# 1WireStamp-V01-006.net
KiCad netlist of a schematic drawn in EAGLE
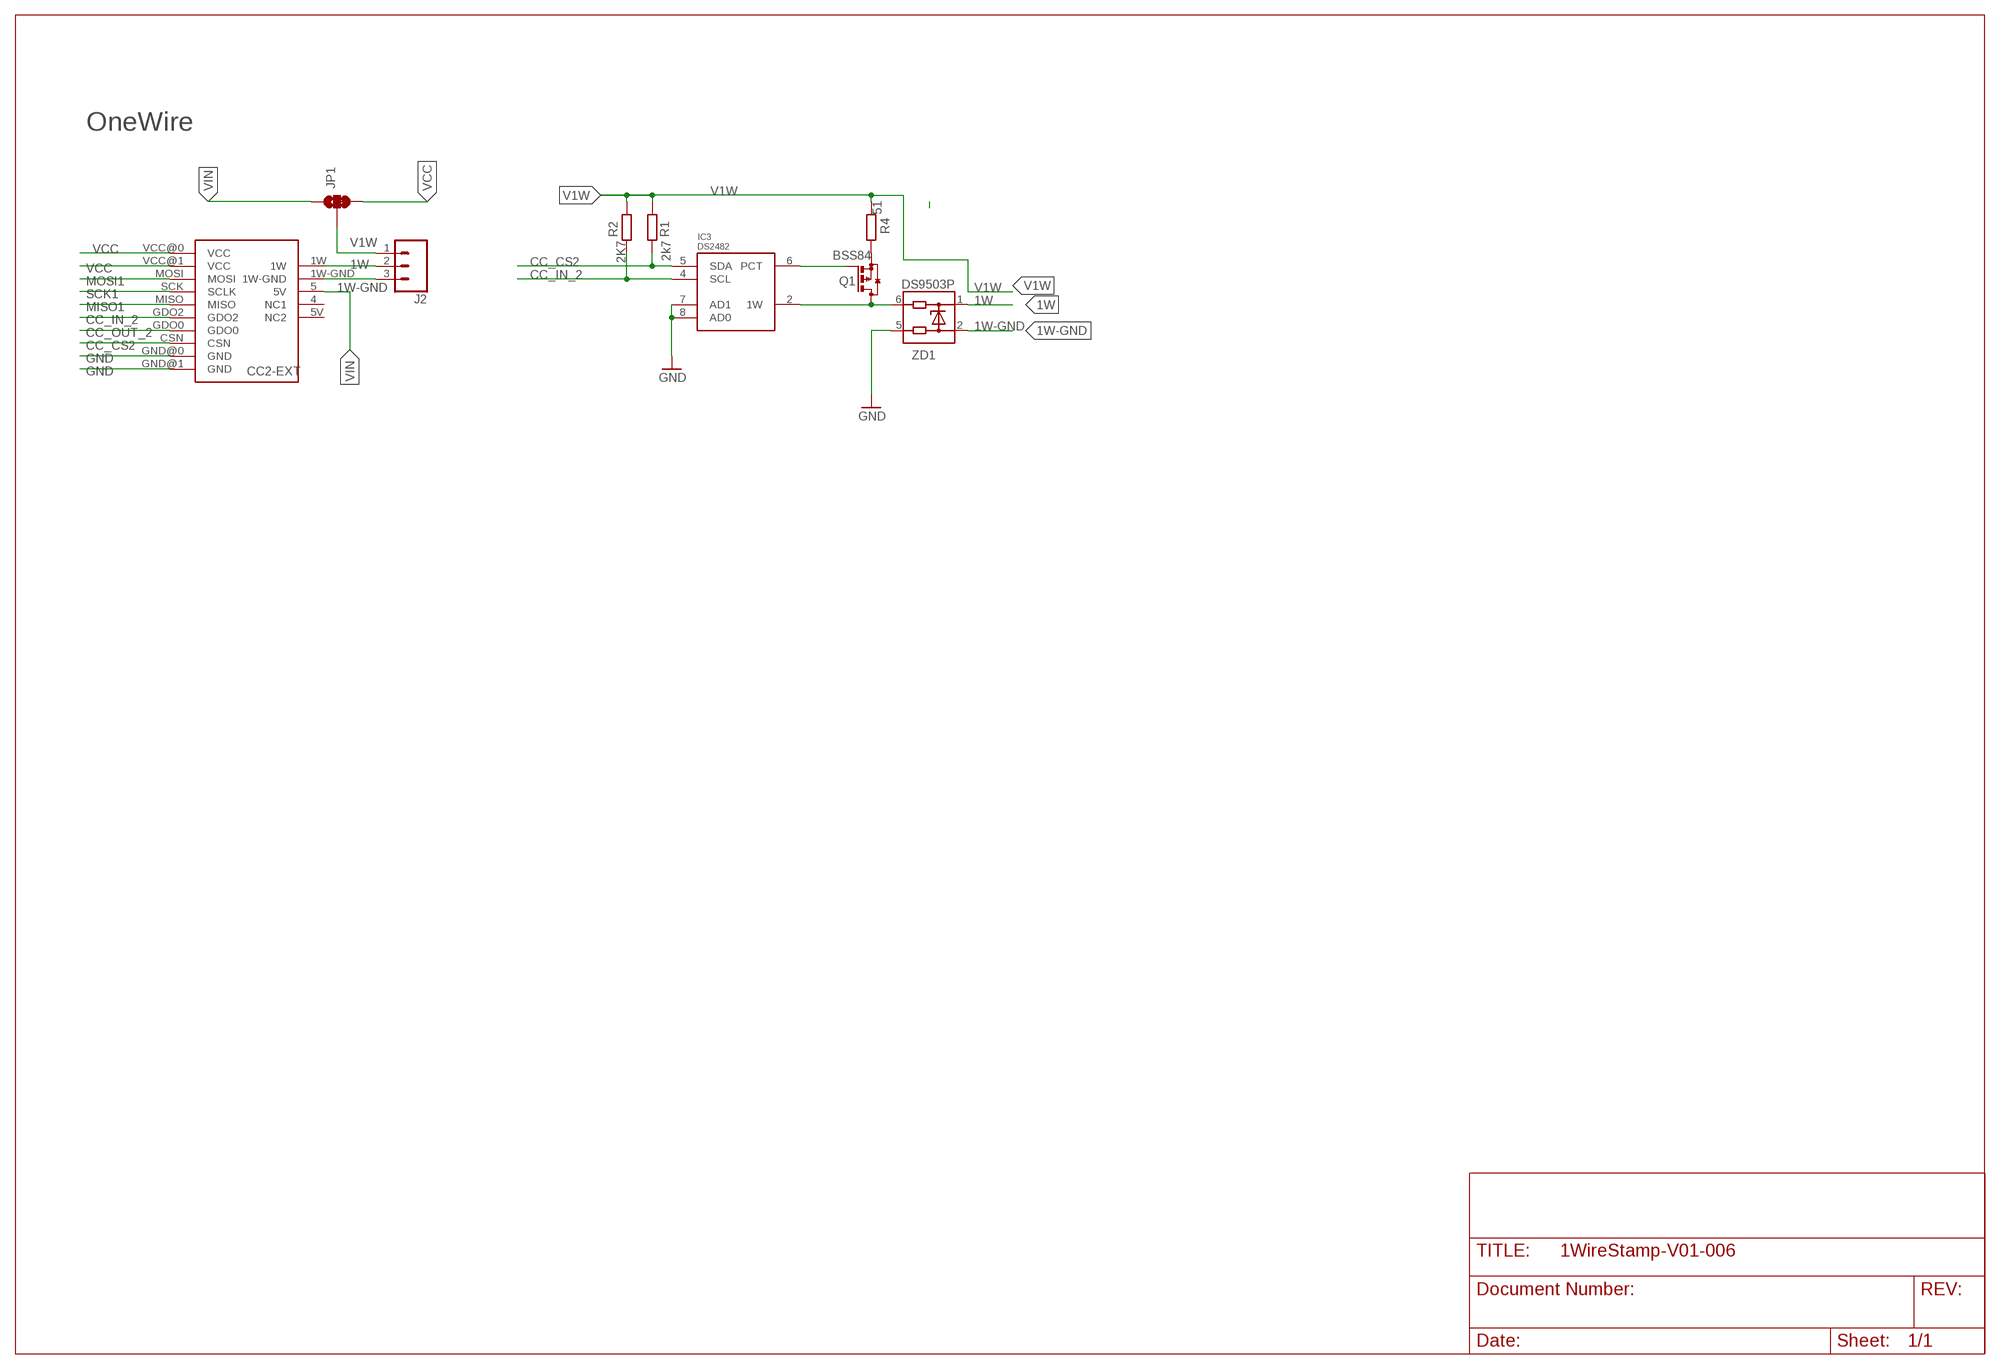
[diagram p0: schematic, sheet 1]

(export (version "E")
  (design (tool "Eeschema 10.0.6"))
  (components
    (comp (ref "CC2-EXT")
      (value "ONEWIRE-MODULEONEWIRE_CC1101_WO-SILK")
      (footprint "eagle-import:ONEWIRE_CC1101_MOD_WO_SILK")
      (libsource (lib "eagle-import") (part "ONEWIRE-MODULEONEWIRE_CC1101_WO-SILK"))
    )
    (comp (ref "IC3")
      (value "DS2482")
      (footprint "eagle-import:SO08")
      (libsource (lib "eagle-import") (part "DS2482-100S"))
    )
    (comp (ref "J2")
      (value "CONN_03LONGPADS")
      (footprint "eagle-import:1X03_LONGPADS")
      (libsource (lib "eagle-import") (part "CONN_03LONGPADS"))
    )
    (comp (ref "JP1")
      (value "JUMPER-SMT_3_1-NC_TRACE_SILK")
      (footprint "eagle-import:SMT-JUMPER_3_1-NC_TRACE_SILK")
      (libsource (lib "eagle-import") (part "JUMPER-SMT_3_1-NC_TRACE_SILK"))
    )
    (comp (ref "Q1")
      (value "BSS84")
      (footprint "eagle-import:SOT23")
      (libsource (lib "eagle-import") (part "BSS84"))
    )
    (comp (ref "R1")
      (value "2k7")
      (footprint "eagle-import:R0805")
      (libsource (lib "eagle-import") (part "R-EU_R0805"))
    )
    (comp (ref "R2")
      (value "2K7")
      (footprint "eagle-import:R0805")
      (libsource (lib "eagle-import") (part "R-EU_R0805"))
    )
    (comp (ref "R4")
      (value "51")
      (footprint "eagle-import:R0805")
      (libsource (lib "eagle-import") (part "R-EU_R0805"))
    )
    (comp (ref "ZD1")
      (value "DS9503P")
      (footprint "eagle-import:TSOC6")
      (libsource (lib "eagle-import") (part "DS9503P"))
    )
  )
  (nets
    (net (code "1") (name "/CC_CS2") (class "Default")
      (node (ref "CC2-EXT") (pin "CSN") (pinfunction "CSN_CSN") (pintype "bidirectional"))
      (node (ref "IC3") (pin "5") (pinfunction "SDA_5") (pintype "bidirectional"))
      (node (ref "R1") (pin "2") (pinfunction "2_2") (pintype "passive"))
    )
    (net (code "2") (name "/CC_IN_2") (class "Default")
      (node (ref "CC2-EXT") (pin "GDO2") (pinfunction "GDO2_GDO2") (pintype "bidirectional"))
      (node (ref "IC3") (pin "4") (pinfunction "SCL_4") (pintype "input"))
      (node (ref "R2") (pin "2") (pinfunction "2_2") (pintype "passive"))
    )
    (net (code "3") (name "/CC_OUT_2") (class "Default")
      (node (ref "CC2-EXT") (pin "GDO0") (pinfunction "GDO0_GDO0") (pintype "bidirectional"))
    )
    (net (code "4") (name "/MISO1") (class "Default")
      (node (ref "CC2-EXT") (pin "MISO") (pinfunction "MISO_MISO") (pintype "bidirectional"))
    )
    (net (code "5") (name "/MOSI1") (class "Default")
      (node (ref "CC2-EXT") (pin "MOSI") (pinfunction "MOSI_MOSI") (pintype "bidirectional"))
    )
    (net (code "6") (name "/SCK1") (class "Default")
      (node (ref "CC2-EXT") (pin "SCK") (pinfunction "SCLK_SCK") (pintype "bidirectional"))
    )
    (net (code "7") (name "1W") (class "Default")
      (node (ref "CC2-EXT") (pin "1W") (pinfunction "1W_1W") (pintype "bidirectional"))
      (node (ref "J2") (pin "2") (pinfunction "2_2") (pintype "passive"))
      (node (ref "ZD1") (pin "1") (pinfunction "P$1_1") (pintype "passive"))
    )
    (net (code "8") (name "1W-GND") (class "Default")
      (node (ref "CC2-EXT") (pin "1W-GND") (pinfunction "1W-GND_1W-GND") (pintype "bidirectional"))
      (node (ref "J2") (pin "3") (pinfunction "3_3") (pintype "passive"))
      (node (ref "ZD1") (pin "2") (pinfunction "P$2_2") (pintype "passive"))
    )
    (net (code "9") (name "GND") (class "Default")
      (node (ref "CC2-EXT") (pin "GND@0") (pinfunction "GND_GND@0") (pintype "power_in"))
      (node (ref "CC2-EXT") (pin "GND@1") (pinfunction "GND_GND@1") (pintype "power_in"))
      (node (ref "IC3") (pin "7") (pinfunction "AD1_7") (pintype "input"))
      (node (ref "IC3") (pin "8") (pinfunction "AD0_8") (pintype "input"))
      (node (ref "ZD1") (pin "5") (pinfunction "P$3_5") (pintype "passive"))
    )
    (net (code "10") (name "Net-(IC3A-1W)") (class "Default")
      (node (ref "IC3") (pin "2") (pinfunction "1W_2") (pintype "open_collector"))
      (node (ref "Q1") (pin "3") (pinfunction "D_3") (pintype "passive"))
      (node (ref "ZD1") (pin "6") (pinfunction "P$4_6") (pintype "passive"))
    )
    (net (code "11") (name "Net-(IC3A-PCT)") (class "Default")
      (node (ref "IC3") (pin "6") (pinfunction "PCT_6") (pintype "output"))
      (node (ref "Q1") (pin "1") (pinfunction "G_1") (pintype "passive"))
    )
    (net (code "12") (name "Net-(Q1-S)") (class "Default")
      (node (ref "Q1") (pin "2") (pinfunction "S_2") (pintype "passive"))
      (node (ref "R4") (pin "1") (pinfunction "1_1") (pintype "passive"))
    )
    (net (code "13") (name "V1W") (class "Default")
      (node (ref "J2") (pin "1") (pinfunction "1_1") (pintype "passive"))
      (node (ref "JP1") (pin "2") (pinfunction "2_2") (pintype "passive"))
      (node (ref "R1") (pin "1") (pinfunction "1_1") (pintype "passive"))
      (node (ref "R2") (pin "1") (pinfunction "1_1") (pintype "passive"))
      (node (ref "R4") (pin "2") (pinfunction "2_2") (pintype "passive"))
    )
    (net (code "14") (name "VCC") (class "Default")
      (node (ref "CC2-EXT") (pin "VCC@0") (pinfunction "VCC_VCC@0") (pintype "power_in"))
      (node (ref "CC2-EXT") (pin "VCC@1") (pinfunction "VCC_VCC@1") (pintype "power_in"))
      (node (ref "JP1") (pin "3") (pinfunction "3_3") (pintype "passive"))
    )
    (net (code "15") (name "VIN") (class "Default")
      (node (ref "CC2-EXT") (pin "5") (pinfunction "5V_5") (pintype "bidirectional"))
      (node (ref "JP1") (pin "1") (pinfunction "1_1") (pintype "passive"))
    )
    (net (code "16") (name "unconnected-(CC2-EXT-NC1-Pad4)") (class "Default")
      (node (ref "CC2-EXT") (pin "4") (pinfunction "NC1_4") (pintype "bidirectional"))
    )
    (net (code "17") (name "unconnected-(CC2-EXT-NC2-Pad5V)") (class "Default")
      (node (ref "CC2-EXT") (pin "5V") (pinfunction "NC2_5V") (pintype "bidirectional"))
    )
  )
)
